# IMU_REV_3.net
KiCad netlist of a schematic drawn in Altium Designer
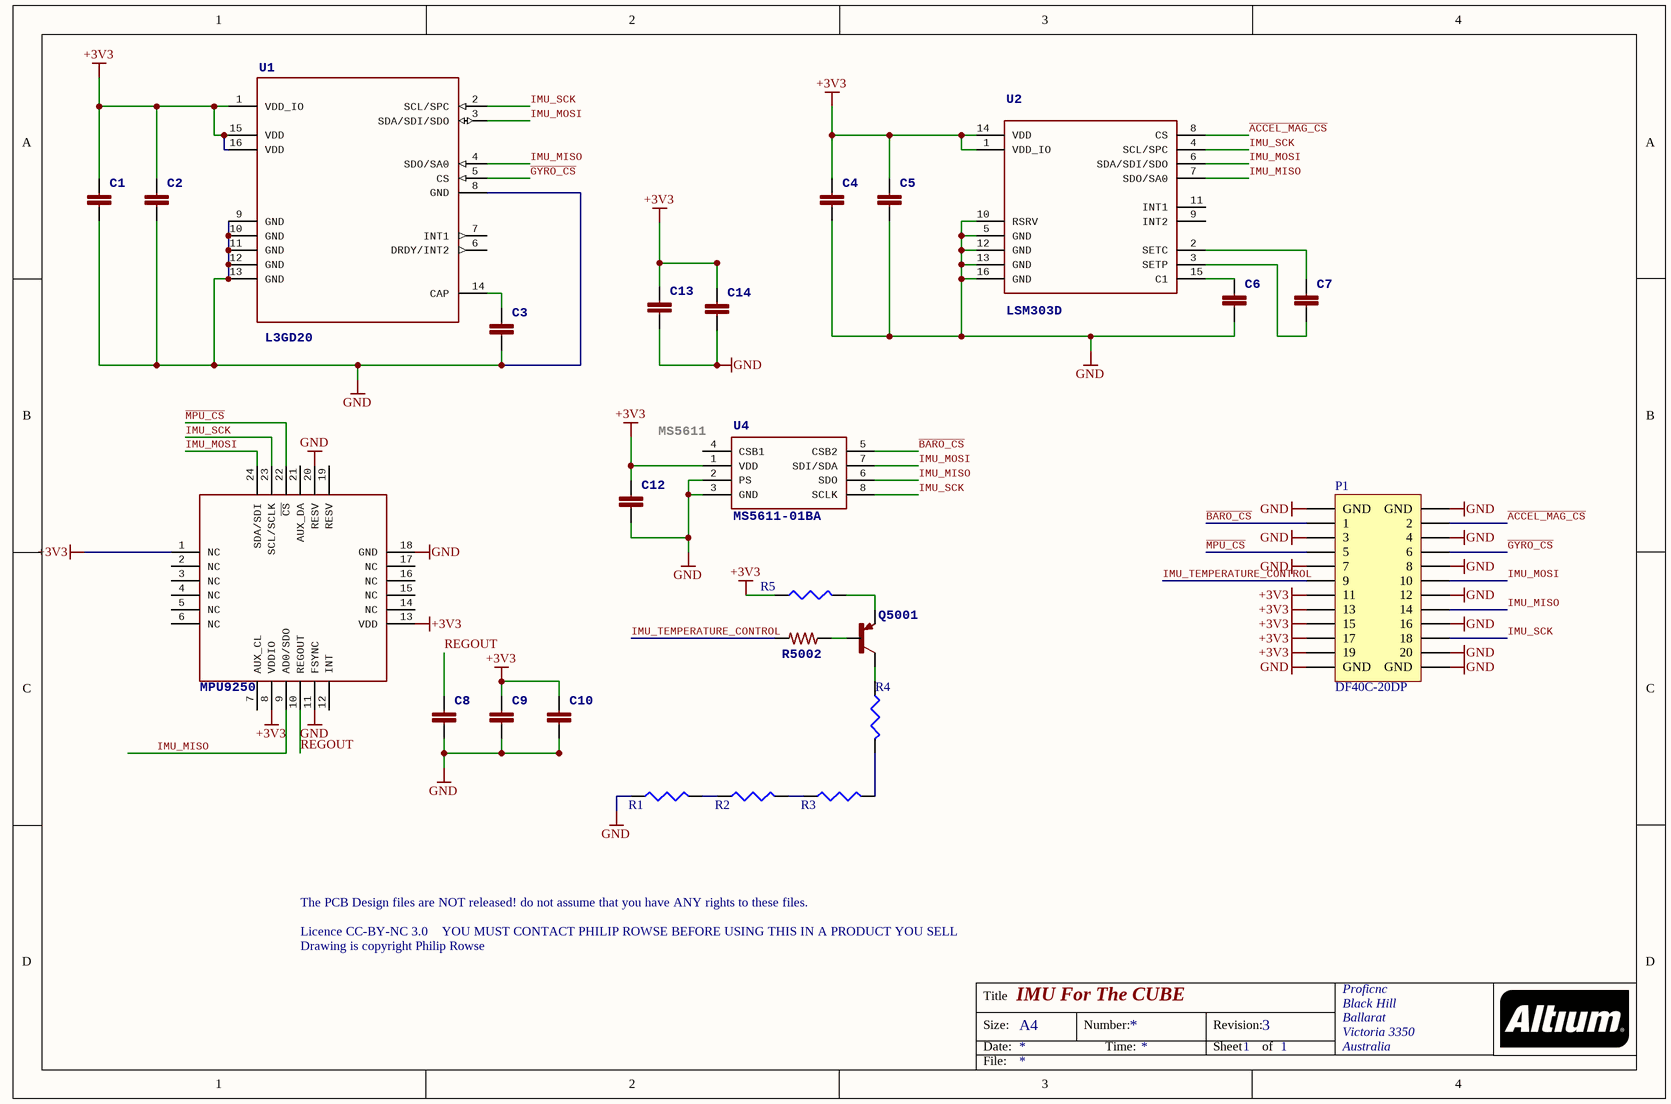
[diagram p0: IMU_REV_3.SchDoc]

(export (version "E")
  (design (tool "Eeschema 10.0.6"))
  (components
    (comp (ref "C1") (value "~") (libsource (lib "altium-import") (part "root_0_CAPACITOR-0805_")))
    (comp (ref "C2") (value "~") (libsource (lib "altium-import") (part "root_0_CAPACITOR-0402_")))
    (comp (ref "C3") (value "~") (libsource (lib "altium-import") (part "root_0_CAPACITOR-0402_")))
    (comp (ref "C4") (value "~") (libsource (lib "altium-import") (part "root_0_CAPACITOR-0805_")))
    (comp (ref "C5") (value "~") (libsource (lib "altium-import") (part "root_0_CAPACITOR-0402_")))
    (comp (ref "C6") (value "~") (libsource (lib "altium-import") (part "root_0_CAPACITOR-0805_")))
    (comp (ref "C7") (value "~") (libsource (lib "altium-import") (part "root_0_CAPACITOR-0402_")))
    (comp (ref "C8") (value "~") (libsource (lib "altium-import") (part "root_0_CAPACITOR-0603_")))
    (comp (ref "C9") (value "~") (libsource (lib "altium-import") (part "root_0_CAPACITOR-0603_")))
    (comp (ref "C10") (value "~") (libsource (lib "altium-import") (part "root_0_CAPACITOR-0402_")))
    (comp (ref "C12") (value "~") (libsource (lib "altium-import") (part "root_0_CAPACITOR-0402_")))
    (comp (ref "C13") (value "~") (libsource (lib "altium-import") (part "root_0_CAPACITOR-0805_")))
    (comp (ref "C14") (value "~") (libsource (lib "altium-import") (part "root_0_CAPACITOR-0402_")))
    (comp (ref "MPU9250") (value "~") (libsource (lib "altium-import") (part "root_0_MPU-6500_")))
    (comp (ref "P1") (value "DF40C-20DP") (libsource (lib "altium-import") (part "root_0_DF40C-20DP_")))
    (comp (ref "Q5001") (value "~") (libsource (lib "altium-import") (part "root_0_MMBT3906*SMD_")))
    (comp (ref "R1") (value "Resistor") (libsource (lib "altium-import") (part "root_1_Resistor_")))
    (comp (ref "R2") (value "Resistor") (libsource (lib "altium-import") (part "root_1_Resistor_")))
    (comp (ref "R3") (value "Resistor") (libsource (lib "altium-import") (part "root_1_Resistor_")))
    (comp (ref "R4") (value "Resistor") (libsource (lib "altium-import") (part "root_0_Resistor_")))
    (comp (ref "R5") (value "Resistor") (libsource (lib "altium-import") (part "root_1_Resistor_")))
    (comp (ref "R5002") (value "~") (libsource (lib "altium-import") (part "root_2_RESISTOR0402-RES_")))
    (comp (ref "U1") (value "L3GD20") (libsource (lib "altium-import") (part "root_0_L3GD20_")))
    (comp (ref "U2") (value "LSM303D") (libsource (lib "altium-import") (part "root_0_LSM303D_")))
    (comp (ref "U4") (value "MS5611-01BA") (libsource (lib "altium-import") (part "root_0_MS5611-01BA_")))
  )
  (nets
    (net (code "1") (name "+3V3") (class "Default")
      (node (ref "C1") (pin "P$1") (pinfunction "1_P$1") (pintype "passive"))
      (node (ref "C10") (pin "P$1") (pinfunction "1_P$1") (pintype "passive"))
      (node (ref "C12") (pin "P$1") (pinfunction "1_P$1") (pintype "passive"))
      (node (ref "C13") (pin "P$1") (pinfunction "1_P$1") (pintype "passive"))
      (node (ref "C14") (pin "P$1") (pinfunction "1_P$1") (pintype "passive"))
      (node (ref "C2") (pin "P$1") (pinfunction "1_P$1") (pintype "passive"))
      (node (ref "C4") (pin "P$1") (pinfunction "1_P$1") (pintype "passive"))
      (node (ref "C5") (pin "P$1") (pinfunction "1_P$1") (pintype "passive"))
      (node (ref "C9") (pin "P$1") (pinfunction "1_P$1") (pintype "passive"))
      (node (ref "MPU9250") (pin "1") (pinfunction "NC_1") (pintype "passive"))
      (node (ref "MPU9250") (pin "13") (pinfunction "VDD_13") (pintype "passive"))
      (node (ref "MPU9250") (pin "8") (pinfunction "VDDIO_8") (pintype "passive"))
      (node (ref "P1") (pin "11") (pinfunction "11_11") (pintype "passive"))
      (node (ref "P1") (pin "13") (pinfunction "13_13") (pintype "passive"))
      (node (ref "P1") (pin "15") (pinfunction "15_15") (pintype "passive"))
      (node (ref "P1") (pin "17") (pinfunction "17_17") (pintype "passive"))
      (node (ref "P1") (pin "19") (pinfunction "19_19") (pintype "passive"))
      (node (ref "R5") (pin "1") (pinfunction "1_1") (pintype "passive"))
      (node (ref "U1") (pin "1") (pinfunction "VDD_IO_1") (pintype "power_in"))
      (node (ref "U1") (pin "15") (pinfunction "VDD_15") (pintype "power_in"))
      (node (ref "U1") (pin "16") (pinfunction "VDD_16") (pintype "power_in"))
      (node (ref "U2") (pin "1") (pinfunction "VDD_IO_1") (pintype "passive"))
      (node (ref "U2") (pin "14") (pinfunction "VDD_14") (pintype "passive"))
      (node (ref "U4") (pin "1") (pinfunction "VDD_1") (pintype "passive"))
    )
    (net (code "2") (name "/IMU_MISO") (class "Default")
      (node (ref "MPU9250") (pin "9") (pinfunction "AD0/SDO_9") (pintype "passive"))
      (node (ref "P1") (pin "14") (pinfunction "14_14") (pintype "passive"))
      (node (ref "U1") (pin "4") (pinfunction "SDO/SA0_4") (pintype "input"))
      (node (ref "U2") (pin "7") (pinfunction "SDO/SA0_7") (pintype "passive"))
      (node (ref "U4") (pin "6") (pinfunction "SDO_6") (pintype "passive"))
    )
    (net (code "3") (name "/IMU_MOSI") (class "Default")
      (node (ref "MPU9250") (pin "24") (pinfunction "SDA/SDI_24") (pintype "passive"))
      (node (ref "P1") (pin "10") (pinfunction "10_10") (pintype "passive"))
      (node (ref "U1") (pin "3") (pinfunction "SDA/SDI/SDO_3") (pintype "bidirectional"))
      (node (ref "U2") (pin "6") (pinfunction "SDA/SDI/SDO_6") (pintype "passive"))
      (node (ref "U4") (pin "7") (pinfunction "SDI/SDA_7") (pintype "passive"))
    )
    (net (code "4") (name "/IMU_SCK") (class "Default")
      (node (ref "MPU9250") (pin "23") (pinfunction "SCL/SCLK_23") (pintype "passive"))
      (node (ref "P1") (pin "18") (pinfunction "18_18") (pintype "passive"))
      (node (ref "U1") (pin "2") (pinfunction "SCL/SPC_2") (pintype "input"))
      (node (ref "U2") (pin "4") (pinfunction "SCL/SPC_4") (pintype "passive"))
      (node (ref "U4") (pin "8") (pinfunction "SCLK_8") (pintype "passive"))
    )
    (net (code "5") (name "/IMU_TEMPERATURE_CONTROL") (class "Default")
      (node (ref "P1") (pin "9") (pinfunction "9_9") (pintype "passive"))
      (node (ref "R5002") (pin "P$2") (pinfunction "2_P$2") (pintype "passive"))
    )
    (net (code "6") (name "/REGOUT") (class "Default")
      (node (ref "C8") (pin "P$1") (pinfunction "1_P$1") (pintype "passive"))
      (node (ref "MPU9250") (pin "10") (pinfunction "REGOUT_10") (pintype "passive"))
    )
    (net (code "7") (name "/~{ACCEL_MAG_CS}") (class "Default")
      (node (ref "P1") (pin "2") (pinfunction "2_2") (pintype "passive"))
      (node (ref "U2") (pin "8") (pinfunction "CS_8") (pintype "passive"))
    )
    (net (code "8") (name "/~{BARO_CS}") (class "Default")
      (node (ref "P1") (pin "1") (pinfunction "1_1") (pintype "passive"))
      (node (ref "U4") (pin "5") (pinfunction "CSB2_5") (pintype "passive"))
    )
    (net (code "9") (name "/~{GYRO_CS}") (class "Default")
      (node (ref "P1") (pin "6") (pinfunction "6_6") (pintype "passive"))
      (node (ref "U1") (pin "5") (pinfunction "CS_5") (pintype "input"))
    )
    (net (code "10") (name "/~{MPU_CS}") (class "Default")
      (node (ref "MPU9250") (pin "22") (pinfunction "~{CS}_22") (pintype "passive"))
      (node (ref "P1") (pin "5") (pinfunction "5_5") (pintype "passive"))
    )
    (net (code "11") (name "GND") (class "Default")
      (node (ref "C1") (pin "P$2") (pinfunction "2_P$2") (pintype "passive"))
      (node (ref "C10") (pin "P$2") (pinfunction "2_P$2") (pintype "passive"))
      (node (ref "C12") (pin "P$2") (pinfunction "2_P$2") (pintype "passive"))
      (node (ref "C13") (pin "P$2") (pinfunction "2_P$2") (pintype "passive"))
      (node (ref "C14") (pin "P$2") (pinfunction "2_P$2") (pintype "passive"))
      (node (ref "C2") (pin "P$2") (pinfunction "2_P$2") (pintype "passive"))
      (node (ref "C3") (pin "P$2") (pinfunction "2_P$2") (pintype "passive"))
      (node (ref "C4") (pin "P$2") (pinfunction "2_P$2") (pintype "passive"))
      (node (ref "C5") (pin "P$2") (pinfunction "2_P$2") (pintype "passive"))
      (node (ref "C6") (pin "P$2") (pinfunction "2_P$2") (pintype "passive"))
      (node (ref "C8") (pin "P$2") (pinfunction "2_P$2") (pintype "passive"))
      (node (ref "C9") (pin "P$2") (pinfunction "2_P$2") (pintype "passive"))
      (node (ref "MPU9250") (pin "11") (pinfunction "FSYNC_11") (pintype "passive"))
      (node (ref "MPU9250") (pin "18") (pinfunction "GND_18") (pintype "passive"))
      (node (ref "MPU9250") (pin "20") (pinfunction "RESV_20") (pintype "passive"))
      (node (ref "P1") (pin "12") (pinfunction "12_12") (pintype "passive"))
      (node (ref "P1") (pin "16") (pinfunction "16_16") (pintype "passive"))
      (node (ref "P1") (pin "20") (pinfunction "20_20") (pintype "passive"))
      (node (ref "P1") (pin "21") (pinfunction "GND_21") (pintype "passive"))
      (node (ref "P1") (pin "22") (pinfunction "GND_22") (pintype "passive"))
      (node (ref "P1") (pin "23") (pinfunction "GND_23") (pintype "passive"))
      (node (ref "P1") (pin "24") (pinfunction "GND_24") (pintype "passive"))
      (node (ref "P1") (pin "3") (pinfunction "3_3") (pintype "passive"))
      (node (ref "P1") (pin "4") (pinfunction "4_4") (pintype "passive"))
      (node (ref "P1") (pin "7") (pinfunction "7_7") (pintype "passive"))
      (node (ref "P1") (pin "8") (pinfunction "8_8") (pintype "passive"))
      (node (ref "R1") (pin "1") (pinfunction "1_1") (pintype "passive"))
      (node (ref "U1") (pin "10") (pinfunction "GND_10") (pintype "power_in"))
      (node (ref "U1") (pin "11") (pinfunction "GND_11") (pintype "power_in"))
      (node (ref "U1") (pin "12") (pinfunction "GND_12") (pintype "power_in"))
      (node (ref "U1") (pin "13") (pinfunction "GND_13") (pintype "power_in"))
      (node (ref "U1") (pin "8") (pinfunction "GND_8") (pintype "power_in"))
      (node (ref "U1") (pin "9") (pinfunction "GND_9") (pintype "power_in"))
      (node (ref "U2") (pin "10") (pinfunction "RSRV_10") (pintype "passive"))
      (node (ref "U2") (pin "12") (pinfunction "GND_12") (pintype "passive"))
      (node (ref "U2") (pin "13") (pinfunction "GND_13") (pintype "passive"))
      (node (ref "U2") (pin "16") (pinfunction "GND_16") (pintype "passive"))
      (node (ref "U2") (pin "5") (pinfunction "GND_5") (pintype "passive"))
      (node (ref "U4") (pin "2") (pinfunction "PS_2") (pintype "passive"))
      (node (ref "U4") (pin "3") (pinfunction "GND_3") (pintype "passive"))
    )
    (net (code "12") (name "Net-(C3-1)") (class "Default")
      (node (ref "C3") (pin "P$1") (pinfunction "1_P$1") (pintype "passive"))
      (node (ref "U1") (pin "14") (pinfunction "CAP_14") (pintype "passive"))
    )
    (net (code "13") (name "Net-(C6-1)") (class "Default")
      (node (ref "C6") (pin "P$1") (pinfunction "1_P$1") (pintype "passive"))
      (node (ref "U2") (pin "15") (pinfunction "C1_15") (pintype "passive"))
    )
    (net (code "14") (name "Net-(C7-1)") (class "Default")
      (node (ref "C7") (pin "P$1") (pinfunction "1_P$1") (pintype "passive"))
      (node (ref "U2") (pin "2") (pinfunction "SETC_2") (pintype "passive"))
    )
    (net (code "15") (name "Net-(C7-2)") (class "Default")
      (node (ref "C7") (pin "P$2") (pinfunction "2_P$2") (pintype "passive"))
      (node (ref "U2") (pin "3") (pinfunction "SETP_3") (pintype "passive"))
    )
    (net (code "16") (name "Net-(Q5001-PadC)") (class "Default")
      (node (ref "Q5001") (pin "C") (pinfunction "C_C") (pintype "passive"))
      (node (ref "R4") (pin "1") (pinfunction "1_1") (pintype "passive"))
    )
    (net (code "17") (name "Net-(Q5001-PadE)") (class "Default")
      (node (ref "Q5001") (pin "E") (pinfunction "E_E") (pintype "passive"))
      (node (ref "R5") (pin "2") (pinfunction "2_2") (pintype "passive"))
    )
    (net (code "18") (name "Net-(R1-Pad2)") (class "Default")
      (node (ref "R1") (pin "2") (pinfunction "2_2") (pintype "passive"))
      (node (ref "R2") (pin "1") (pinfunction "1_1") (pintype "passive"))
    )
    (net (code "19") (name "Net-(R2-Pad2)") (class "Default")
      (node (ref "R2") (pin "2") (pinfunction "2_2") (pintype "passive"))
      (node (ref "R3") (pin "1") (pinfunction "1_1") (pintype "passive"))
    )
    (net (code "20") (name "Net-(R3-Pad2)") (class "Default")
      (node (ref "R3") (pin "2") (pinfunction "2_2") (pintype "passive"))
      (node (ref "R4") (pin "2") (pinfunction "2_2") (pintype "passive"))
    )
    (net (code "21") (name "Net-(R5002-1)") (class "Default")
      (node (ref "Q5001") (pin "B") (pinfunction "B_B") (pintype "passive"))
      (node (ref "R5002") (pin "P$1") (pinfunction "1_P$1") (pintype "passive"))
    )
    (net (code "22") (name "unconnected-(MPU9250-AUX_CL-Pad7)") (class "Default")
      (node (ref "MPU9250") (pin "7") (pinfunction "AUX_CL_7") (pintype "passive"))
    )
    (net (code "23") (name "unconnected-(MPU9250-AUX_DA-Pad21)") (class "Default")
      (node (ref "MPU9250") (pin "21") (pinfunction "AUX_DA_21") (pintype "passive"))
    )
    (net (code "24") (name "unconnected-(MPU9250-INT-Pad12)") (class "Default")
      (node (ref "MPU9250") (pin "12") (pinfunction "INT_12") (pintype "passive"))
    )
    (net (code "25") (name "unconnected-(MPU9250-NC-Pad2)") (class "Default")
      (node (ref "MPU9250") (pin "2") (pinfunction "NC_2") (pintype "passive"))
    )
    (net (code "26") (name "unconnected-(MPU9250-NC-Pad3)") (class "Default")
      (node (ref "MPU9250") (pin "3") (pinfunction "NC_3") (pintype "passive"))
    )
    (net (code "27") (name "unconnected-(MPU9250-NC-Pad4)") (class "Default")
      (node (ref "MPU9250") (pin "4") (pinfunction "NC_4") (pintype "passive"))
    )
    (net (code "28") (name "unconnected-(MPU9250-NC-Pad5)") (class "Default")
      (node (ref "MPU9250") (pin "5") (pinfunction "NC_5") (pintype "passive"))
    )
    (net (code "29") (name "unconnected-(MPU9250-NC-Pad6)") (class "Default")
      (node (ref "MPU9250") (pin "6") (pinfunction "NC_6") (pintype "passive"))
    )
    (net (code "30") (name "unconnected-(MPU9250-NC-Pad14)") (class "Default")
      (node (ref "MPU9250") (pin "14") (pinfunction "NC_14") (pintype "passive"))
    )
    (net (code "31") (name "unconnected-(MPU9250-NC-Pad15)") (class "Default")
      (node (ref "MPU9250") (pin "15") (pinfunction "NC_15") (pintype "passive"))
    )
    (net (code "32") (name "unconnected-(MPU9250-NC-Pad16)") (class "Default")
      (node (ref "MPU9250") (pin "16") (pinfunction "NC_16") (pintype "passive"))
    )
    (net (code "33") (name "unconnected-(MPU9250-NC-Pad17)") (class "Default")
      (node (ref "MPU9250") (pin "17") (pinfunction "NC_17") (pintype "passive"))
    )
    (net (code "34") (name "unconnected-(MPU9250-RESV-Pad19)") (class "Default")
      (node (ref "MPU9250") (pin "19") (pinfunction "RESV_19") (pintype "passive"))
    )
    (net (code "35") (name "unconnected-(U1-DRDY{slash}INT2-Pad6)") (class "Default")
      (node (ref "U1") (pin "6") (pinfunction "DRDY/INT2_6") (pintype "output"))
    )
    (net (code "36") (name "unconnected-(U1-INT1-Pad7)") (class "Default")
      (node (ref "U1") (pin "7") (pinfunction "INT1_7") (pintype "output"))
    )
    (net (code "37") (name "unconnected-(U2-INT1-Pad11)") (class "Default")
      (node (ref "U2") (pin "11") (pinfunction "INT1_11") (pintype "passive"))
    )
    (net (code "38") (name "unconnected-(U2-INT2-Pad9)") (class "Default")
      (node (ref "U2") (pin "9") (pinfunction "INT2_9") (pintype "passive"))
    )
    (net (code "39") (name "unconnected-(U4-CSB1-Pad4)") (class "Default")
      (node (ref "U4") (pin "4") (pinfunction "CSB1_4") (pintype "passive"))
    )
  )
)
